# Inductor-based_non-neighbor_balancing_ar.net
KiCad netlist of a schematic drawn in EAGLE
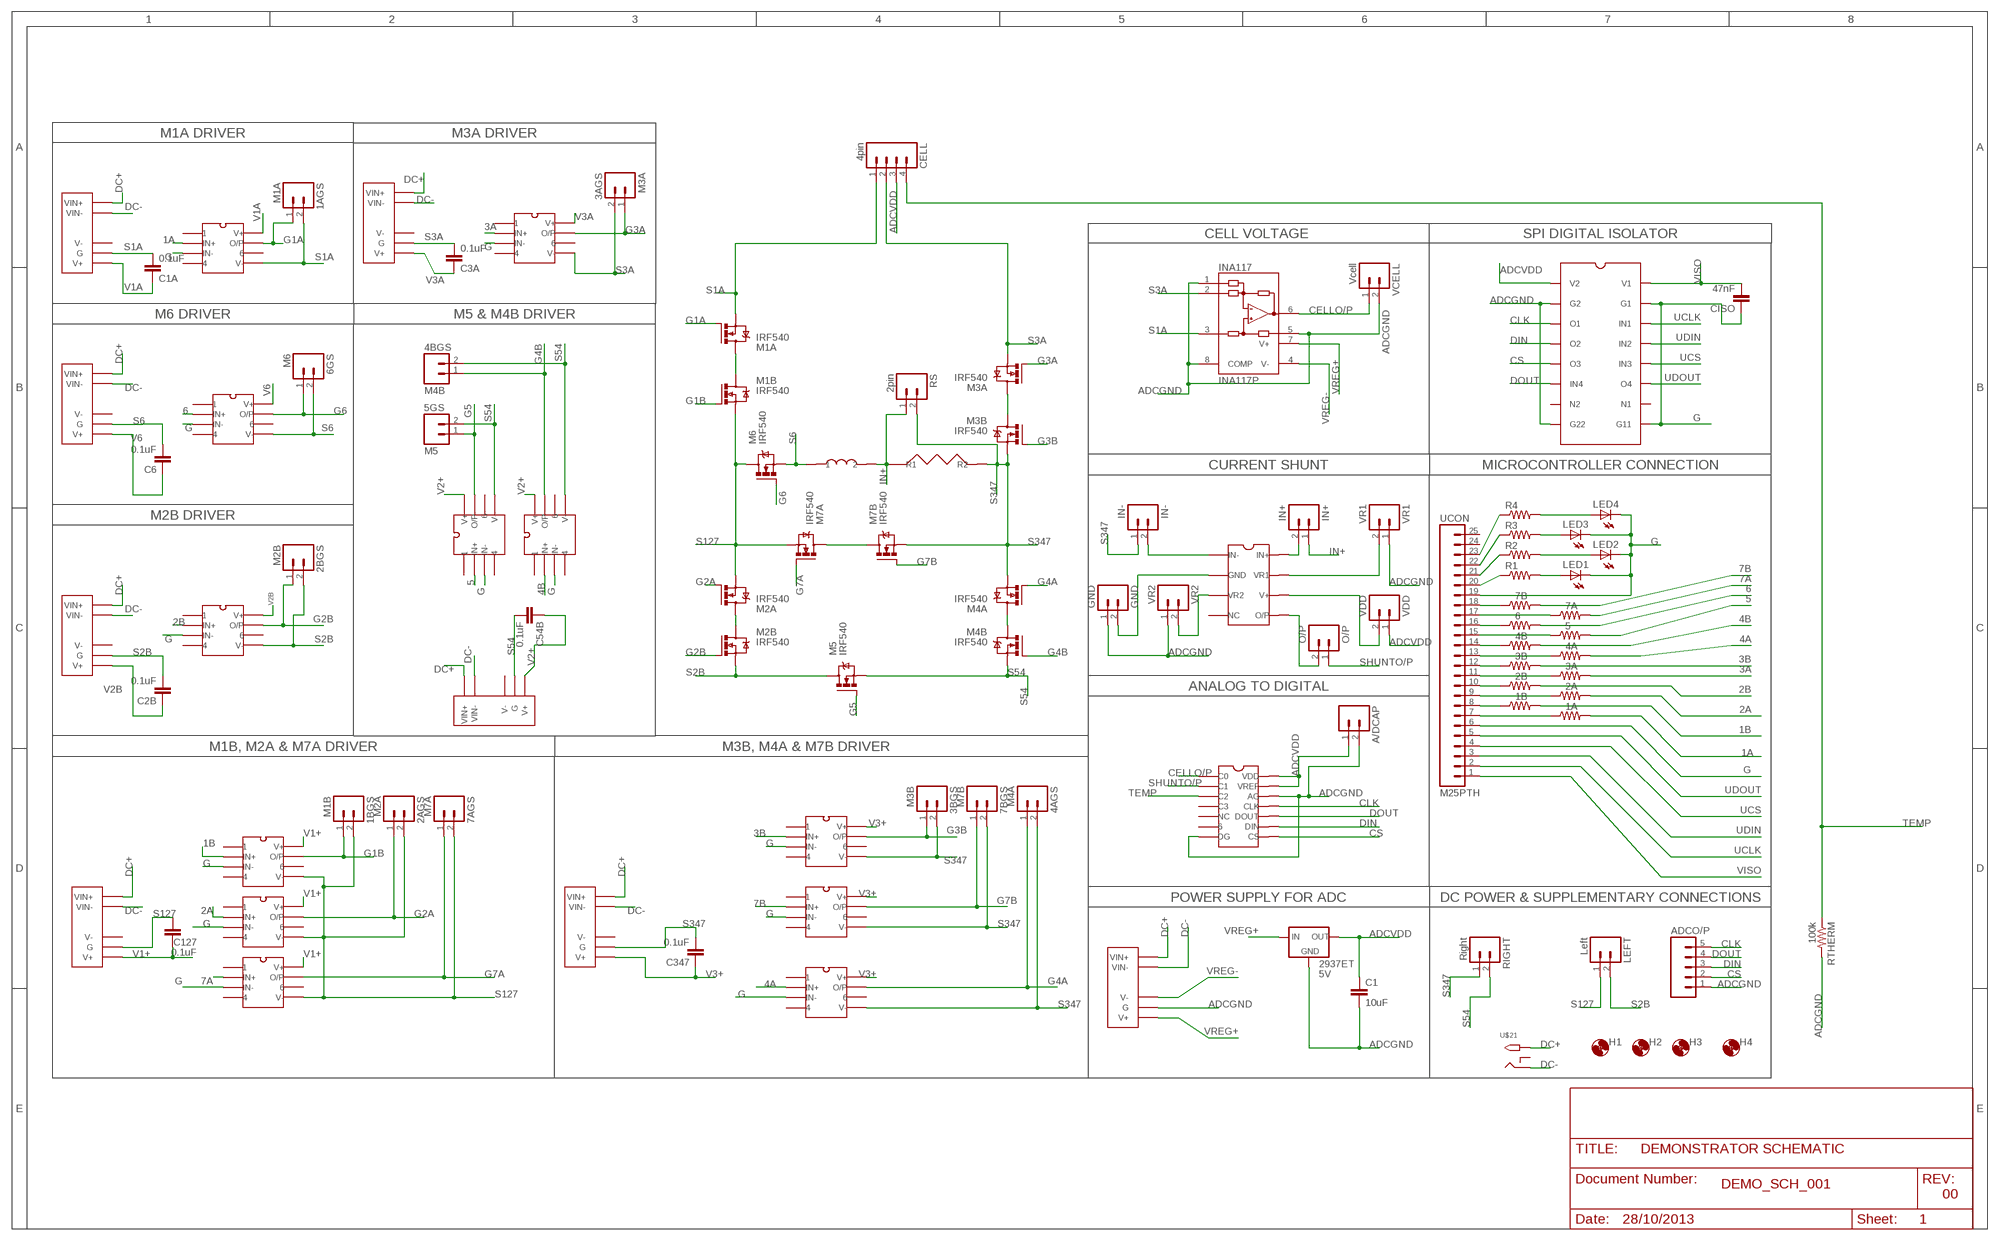
[diagram p0: schematic, sheet 1]

(export (version "E")
  (design (tool "Eeschema 10.0.6"))
  (components
    (comp (ref "1A")
      (value "220")
      (footprint "eagle-import:AXIAL-0.5")
      (libsource (lib "eagle-import") (part "RESISTORPTH-1/2W"))
    )
    (comp (ref "1AGS")
      (value "M1A")
      (footprint "eagle-import:1X02")
      (libsource (lib "eagle-import") (part "M02PTH"))
    )
    (comp (ref "1B")
      (value "220")
      (footprint "eagle-import:AXIAL-0.5")
      (libsource (lib "eagle-import") (part "RESISTORPTH-1/2W"))
    )
    (comp (ref "1BGS")
      (value "M1B")
      (footprint "eagle-import:1X02")
      (libsource (lib "eagle-import") (part "M02PTH"))
    )
    (comp (ref "2A")
      (value "220")
      (footprint "eagle-import:AXIAL-0.5")
      (libsource (lib "eagle-import") (part "RESISTORPTH-1/2W"))
    )
    (comp (ref "2AGS")
      (value "M2A")
      (footprint "eagle-import:1X02")
      (libsource (lib "eagle-import") (part "M02PTH"))
    )
    (comp (ref "2B")
      (value "220")
      (footprint "eagle-import:AXIAL-0.5")
      (libsource (lib "eagle-import") (part "RESISTORPTH-1/2W"))
    )
    (comp (ref "2BGS")
      (value "M2B")
      (footprint "eagle-import:1X02")
      (libsource (lib "eagle-import") (part "M02PTH"))
    )
    (comp (ref "3A")
      (value "220")
      (footprint "eagle-import:AXIAL-0.5")
      (libsource (lib "eagle-import") (part "RESISTORPTH-1/2W"))
    )
    (comp (ref "3AGS")
      (value "M3A")
      (footprint "eagle-import:1X02")
      (libsource (lib "eagle-import") (part "M02PTH"))
    )
    (comp (ref "3B")
      (value "220")
      (footprint "eagle-import:AXIAL-0.5")
      (libsource (lib "eagle-import") (part "RESISTORPTH-1/2W"))
    )
    (comp (ref "3BGS")
      (value "M3B")
      (footprint "eagle-import:1X02")
      (libsource (lib "eagle-import") (part "M02PTH"))
    )
    (comp (ref "4A")
      (value "220")
      (footprint "eagle-import:AXIAL-0.5")
      (libsource (lib "eagle-import") (part "RESISTORPTH-1/2W"))
    )
    (comp (ref "4AGS")
      (value "M4A")
      (footprint "eagle-import:1X02")
      (libsource (lib "eagle-import") (part "M02PTH"))
    )
    (comp (ref "4B")
      (value "220")
      (footprint "eagle-import:AXIAL-0.5")
      (libsource (lib "eagle-import") (part "RESISTORPTH-1/2W"))
    )
    (comp (ref "4BGS")
      (value "M4B")
      (footprint "eagle-import:1X02")
      (libsource (lib "eagle-import") (part "M02PTH"))
    )
    (comp (ref "5")
      (value "220")
      (footprint "eagle-import:AXIAL-0.5")
      (libsource (lib "eagle-import") (part "RESISTORPTH-1/2W"))
    )
    (comp (ref "5GS")
      (value "M5")
      (footprint "eagle-import:1X02")
      (libsource (lib "eagle-import") (part "M02PTH"))
    )
    (comp (ref "6")
      (value "220")
      (footprint "eagle-import:AXIAL-0.5")
      (libsource (lib "eagle-import") (part "RESISTORPTH-1/2W"))
    )
    (comp (ref "6GS")
      (value "M6")
      (footprint "eagle-import:1X02")
      (libsource (lib "eagle-import") (part "M02PTH"))
    )
    (comp (ref "7A")
      (value "220")
      (footprint "eagle-import:AXIAL-0.5")
      (libsource (lib "eagle-import") (part "RESISTORPTH-1/2W"))
    )
    (comp (ref "7AGS")
      (value "M7A")
      (footprint "eagle-import:1X02")
      (libsource (lib "eagle-import") (part "M02PTH"))
    )
    (comp (ref "7B")
      (value "220")
      (footprint "eagle-import:AXIAL-0.5")
      (libsource (lib "eagle-import") (part "RESISTORPTH-1/2W"))
    )
    (comp (ref "7BGS")
      (value "M7B")
      (footprint "eagle-import:1X02")
      (libsource (lib "eagle-import") (part "M02PTH"))
    )
    (comp (ref "2937ET")
      (value "5V")
      (footprint "eagle-import:78XXS")
      (libsource (lib "eagle-import") (part "78XXS"))
    )
    (comp (ref "A/DCAP")
      (value "M02PTH")
      (footprint "eagle-import:1X02")
      (libsource (lib "eagle-import") (part "M02PTH"))
    )
    (comp (ref "AD8210")
      (value "CSM")
      (footprint "eagle-import:CSM")
      (libsource (lib "eagle-import") (part "CSM"))
    )
    (comp (ref "ADC")
      (value "ADC")
      (footprint "eagle-import:DIL14")
      (libsource (lib "eagle-import") (part "ADC"))
    )
    (comp (ref "ADCO/P")
      (value "M05PTH")
      (footprint "eagle-import:1X05")
      (libsource (lib "eagle-import") (part "M05PTH"))
    )
    (comp (ref "C1")
      (value "10uF")
      (footprint "eagle-import:CAP-PTH-5MM")
      (libsource (lib "eagle-import") (part "CAPPTH1"))
    )
    (comp (ref "C1A")
      (value "0.1uF")
      (footprint "eagle-import:CAP-PTH-5MM")
      (libsource (lib "eagle-import") (part "SparkFun-Passives_CAPPTH1"))
    )
    (comp (ref "C2B")
      (value "0.1uF")
      (footprint "eagle-import:CAP-PTH-5MM")
      (libsource (lib "eagle-import") (part "SparkFun-Passives_CAPPTH1"))
    )
    (comp (ref "C3A")
      (value "0.1uF")
      (footprint "eagle-import:CAP-PTH-5MM")
      (libsource (lib "eagle-import") (part "SparkFun-Passives_CAPPTH1"))
    )
    (comp (ref "C6")
      (value "0.1uF")
      (footprint "eagle-import:CAP-PTH-5MM")
      (libsource (lib "eagle-import") (part "SparkFun-Passives_CAPPTH1"))
    )
    (comp (ref "C54B")
      (value "0.1uF")
      (footprint "eagle-import:CAP-PTH-5MM")
      (libsource (lib "eagle-import") (part "SparkFun-Passives_CAPPTH1"))
    )
    (comp (ref "C127")
      (value "0.1uF")
      (footprint "eagle-import:CAP-PTH-5MM")
      (libsource (lib "eagle-import") (part "SparkFun-Passives_CAPPTH1"))
    )
    (comp (ref "C347")
      (value "0.1uF")
      (footprint "eagle-import:CAP-PTH-5MM")
      (libsource (lib "eagle-import") (part "SparkFun-Passives_CAPPTH1"))
    )
    (comp (ref "CELL")
      (value "4pin")
      (footprint "eagle-import:1X04")
      (libsource (lib "eagle-import") (part "M04PTH"))
    )
    (comp (ref "CISO")
      (value "47nF")
      (footprint "eagle-import:CAP-PTH-5MM")
      (libsource (lib "eagle-import") (part "SparkFun-Passives_CAPPTH1"))
    )
    (comp (ref "DC/DC-ADC")
      (value "ADC")
      (footprint "eagle-import:DC-DC")
      (libsource (lib "eagle-import") (part "DC-DC"))
    )
    (comp (ref "DC/DC1A")
      (value "1A")
      (footprint "eagle-import:DC-DC")
      (libsource (lib "eagle-import") (part "DC-DC"))
    )
    (comp (ref "DC/DC2B")
      (value "2B")
      (footprint "eagle-import:DC-DC")
      (libsource (lib "eagle-import") (part "DC-DC"))
    )
    (comp (ref "DC/DC3A")
      (value "3A")
      (footprint "eagle-import:DC-DC")
      (libsource (lib "eagle-import") (part "DC-DC"))
    )
    (comp (ref "DC/DC6")
      (value "6")
      (footprint "eagle-import:DC-DC")
      (libsource (lib "eagle-import") (part "DC-DC"))
    )
    (comp (ref "DC/DC45")
      (value "4B5")
      (footprint "eagle-import:DC-DC")
      (libsource (lib "eagle-import") (part "DC-DC"))
    )
    (comp (ref "DC/DC127")
      (value "1B2A7A")
      (footprint "eagle-import:DC-DC")
      (libsource (lib "eagle-import") (part "DC-DC"))
    )
    (comp (ref "DC/DC347")
      (value "3B4A7B")
      (footprint "eagle-import:DC-DC")
      (libsource (lib "eagle-import") (part "DC-DC"))
    )
    (comp (ref "GND")
      (value "GND")
      (footprint "eagle-import:1X02")
      (libsource (lib "eagle-import") (part "M02PTH"))
    )
    (comp (ref "H1")
      (value "MOUNT-HOLE3.0")
      (footprint "eagle-import:3,0")
      (libsource (lib "eagle-import") (part "MOUNT-HOLE3.0"))
    )
    (comp (ref "H2")
      (value "MOUNT-HOLE3.0")
      (footprint "eagle-import:3,0")
      (libsource (lib "eagle-import") (part "MOUNT-HOLE3.0"))
    )
    (comp (ref "H3")
      (value "MOUNT-HOLE3.0")
      (footprint "eagle-import:3,0")
      (libsource (lib "eagle-import") (part "MOUNT-HOLE3.0"))
    )
    (comp (ref "H4")
      (value "MOUNT-HOLE3.0")
      (footprint "eagle-import:3,0")
      (libsource (lib "eagle-import") (part "MOUNT-HOLE3.0"))
    )
    (comp (ref "HCPL902J")
      (value "HCPL902")
      (footprint "eagle-import:HCPL902")
      (libsource (lib "eagle-import") (part "HCPL902"))
    )
    (comp (ref "IN+")
      (value "IN+")
      (footprint "eagle-import:1X02")
      (libsource (lib "eagle-import") (part "M02PTH"))
    )
    (comp (ref "IN-")
      (value "IN-")
      (footprint "eagle-import:1X02")
      (libsource (lib "eagle-import") (part "M02PTH"))
    )
    (comp (ref "INA117")
      (value "INA117P")
      (footprint "eagle-import:DIL08")
      (fields (field (name "MF") "TEXAS INSTRUMENTS"))
      (libsource (lib "eagle-import") (part "INA117P"))
    )
    (comp (ref "LED1")
      (value "LEDCHIPLED_0805")
      (footprint "eagle-import:CHIPLED_0805")
      (libsource (lib "eagle-import") (part "LEDCHIPLED_0805"))
    )
    (comp (ref "LED2")
      (value "LEDCHIPLED_0805")
      (footprint "eagle-import:CHIPLED_0805")
      (libsource (lib "eagle-import") (part "LEDCHIPLED_0805"))
    )
    (comp (ref "LED3")
      (value "LEDCHIPLED_0805")
      (footprint "eagle-import:CHIPLED_0805")
      (libsource (lib "eagle-import") (part "LEDCHIPLED_0805"))
    )
    (comp (ref "LED4")
      (value "LEDCHIPLED_0805")
      (footprint "eagle-import:CHIPLED_0805")
      (libsource (lib "eagle-import") (part "LEDCHIPLED_0805"))
    )
    (comp (ref "LEFT")
      (value "Left")
      (footprint "eagle-import:1X02")
      (libsource (lib "eagle-import") (part "M02PTH"))
    )
    (comp (ref "M1A")
      (value "IRF540")
      (footprint "eagle-import:TO220BV")
      (libsource (lib "eagle-import") (part "IRF540"))
    )
    (comp (ref "M1AD")
      (value "M1A")
      (footprint "eagle-import:OPTO3180")
      (libsource (lib "eagle-import") (part "OPTO3180"))
    )
    (comp (ref "M1B")
      (value "IRF540")
      (footprint "eagle-import:TO220BV")
      (libsource (lib "eagle-import") (part "IRF540"))
    )
    (comp (ref "M1BD")
      (value "M1B")
      (footprint "eagle-import:OPTO3180")
      (libsource (lib "eagle-import") (part "OPTO3180"))
    )
    (comp (ref "M2A")
      (value "IRF540")
      (footprint "eagle-import:TO220BV")
      (libsource (lib "eagle-import") (part "IRF540"))
    )
    (comp (ref "M2AD")
      (value "M2A")
      (footprint "eagle-import:OPTO3180")
      (libsource (lib "eagle-import") (part "OPTO3180"))
    )
    (comp (ref "M2B")
      (value "IRF540")
      (footprint "eagle-import:TO220BV")
      (libsource (lib "eagle-import") (part "IRF540"))
    )
    (comp (ref "M2BD")
      (value "M2B")
      (footprint "eagle-import:OPTO3180")
      (libsource (lib "eagle-import") (part "OPTO3180"))
    )
    (comp (ref "M3A")
      (value "IRF540")
      (footprint "eagle-import:TO220BV")
      (libsource (lib "eagle-import") (part "IRF540"))
    )
    (comp (ref "M3AD")
      (value "M3A")
      (footprint "eagle-import:OPTO3180")
      (libsource (lib "eagle-import") (part "OPTO3180"))
    )
    (comp (ref "M3B")
      (value "IRF540")
      (footprint "eagle-import:TO220BV")
      (libsource (lib "eagle-import") (part "IRF540"))
    )
    (comp (ref "M3BD")
      (value "M3B")
      (footprint "eagle-import:OPTO3180")
      (libsource (lib "eagle-import") (part "OPTO3180"))
    )
    (comp (ref "M4A")
      (value "IRF540")
      (footprint "eagle-import:TO220BV")
      (libsource (lib "eagle-import") (part "IRF540"))
    )
    (comp (ref "M4AD")
      (value "M4A")
      (footprint "eagle-import:OPTO3180")
      (libsource (lib "eagle-import") (part "OPTO3180"))
    )
    (comp (ref "M4B")
      (value "IRF540")
      (footprint "eagle-import:TO220BV")
      (libsource (lib "eagle-import") (part "IRF540"))
    )
    (comp (ref "M4BD")
      (value "M4B")
      (footprint "eagle-import:OPTO3180")
      (libsource (lib "eagle-import") (part "OPTO3180"))
    )
    (comp (ref "M5")
      (value "IRF540")
      (footprint "eagle-import:TO220BV")
      (libsource (lib "eagle-import") (part "IRF540"))
    )
    (comp (ref "M5D")
      (value "M5")
      (footprint "eagle-import:OPTO3180")
      (libsource (lib "eagle-import") (part "OPTO3180"))
    )
    (comp (ref "M6")
      (value "IRF540")
      (footprint "eagle-import:TO220BV")
      (libsource (lib "eagle-import") (part "IRF540"))
    )
    (comp (ref "M6D")
      (value "M6")
      (footprint "eagle-import:OPTO3180")
      (libsource (lib "eagle-import") (part "OPTO3180"))
    )
    (comp (ref "M7A")
      (value "IRF540")
      (footprint "eagle-import:TO220BV")
      (libsource (lib "eagle-import") (part "IRF540"))
    )
    (comp (ref "M7AD")
      (value "M7A")
      (footprint "eagle-import:OPTO3180")
      (libsource (lib "eagle-import") (part "OPTO3180"))
    )
    (comp (ref "M7B")
      (value "IRF540")
      (footprint "eagle-import:TO220BV")
      (libsource (lib "eagle-import") (part "IRF540"))
    )
    (comp (ref "M7BD")
      (value "M7B")
      (footprint "eagle-import:OPTO3180")
      (libsource (lib "eagle-import") (part "OPTO3180"))
    )
    (comp (ref "O/P")
      (value "O/P")
      (footprint "eagle-import:1X02")
      (libsource (lib "eagle-import") (part "M02PTH"))
    )
    (comp (ref "R1")
      (value "R-US_R0805")
      (footprint "eagle-import:R0805")
      (libsource (lib "eagle-import") (part "R-US_R0805"))
    )
    (comp (ref "R2")
      (value "R-US_R0805")
      (footprint "eagle-import:R0805")
      (libsource (lib "eagle-import") (part "R-US_R0805"))
    )
    (comp (ref "R3")
      (value "R-US_R0805")
      (footprint "eagle-import:R0805")
      (libsource (lib "eagle-import") (part "R-US_R0805"))
    )
    (comp (ref "R4")
      (value "R-US_R0805")
      (footprint "eagle-import:R0805")
      (libsource (lib "eagle-import") (part "R-US_R0805"))
    )
    (comp (ref "RIGHT")
      (value "Right")
      (footprint "eagle-import:1X02")
      (libsource (lib "eagle-import") (part "M02PTH"))
    )
    (comp (ref "RS")
      (value "2pin")
      (footprint "eagle-import:1X02")
      (libsource (lib "eagle-import") (part "M02PTH"))
    )
    (comp (ref "RTHERM")
      (value "100k")
      (footprint "eagle-import:AXIAL-0.5")
      (libsource (lib "eagle-import") (part "RESISTORPTH-1/2W"))
    )
    (comp (ref "U$1")
      (value "INDFINAL")
      (footprint "eagle-import:IND1MHFINAL")
      (libsource (lib "eagle-import") (part "INDFINAL"))
    )
    (comp (ref "U$3")
      (value "RSHUNT")
      (footprint "eagle-import:RSHUNT")
      (libsource (lib "eagle-import") (part "RSHUNT"))
    )
    (comp (ref "U$21")
      (value "2.1MMJACKTHM")
      (footprint "eagle-import:PJ-102A")
      (libsource (lib "eagle-import") (part "2.1MMJACKTHM"))
    )
    (comp (ref "UCON")
      (value "M25PTH")
      (footprint "eagle-import:1X25")
      (libsource (lib "eagle-import") (part "M25PTH"))
    )
    (comp (ref "VCELL")
      (value "Vcell")
      (footprint "eagle-import:1X02")
      (libsource (lib "eagle-import") (part "M02PTH"))
    )
    (comp (ref "VDD")
      (value "VDD")
      (footprint "eagle-import:1X02")
      (libsource (lib "eagle-import") (part "M02PTH"))
    )
    (comp (ref "VR1")
      (value "VR1")
      (footprint "eagle-import:1X02")
      (libsource (lib "eagle-import") (part "M02PTH"))
    )
    (comp (ref "VR2")
      (value "VR2")
      (footprint "eagle-import:1X02")
      (libsource (lib "eagle-import") (part "M02PTH"))
    )
  )
  (nets
    (net (code "1") (name "/1A") (class "Default")
      (node (ref "1A") (pin "P$2") (pinfunction "2_P$2") (pintype "passive"))
      (node (ref "M1AD") (pin "IN+") (pinfunction "IN+_IN+") (pintype "bidirectional"))
    )
    (net (code "2") (name "/1B") (class "Default")
      (node (ref "1B") (pin "P$2") (pinfunction "2_P$2") (pintype "passive"))
      (node (ref "M1BD") (pin "IN+") (pinfunction "IN+_IN+") (pintype "bidirectional"))
    )
    (net (code "3") (name "/2A") (class "Default")
      (node (ref "2A") (pin "P$2") (pinfunction "2_P$2") (pintype "passive"))
      (node (ref "M2AD") (pin "IN+") (pinfunction "IN+_IN+") (pintype "bidirectional"))
    )
    (net (code "4") (name "/2B") (class "Default")
      (node (ref "2B") (pin "P$2") (pinfunction "2_P$2") (pintype "passive"))
      (node (ref "M2BD") (pin "IN+") (pinfunction "IN+_IN+") (pintype "bidirectional"))
    )
    (net (code "5") (name "/3A") (class "Default")
      (node (ref "3A") (pin "P$2") (pinfunction "2_P$2") (pintype "passive"))
      (node (ref "M3AD") (pin "IN+") (pinfunction "IN+_IN+") (pintype "bidirectional"))
    )
    (net (code "6") (name "/3B") (class "Default")
      (node (ref "3B") (pin "P$2") (pinfunction "2_P$2") (pintype "passive"))
      (node (ref "M3BD") (pin "IN+") (pinfunction "IN+_IN+") (pintype "bidirectional"))
    )
    (net (code "7") (name "/4A") (class "Default")
      (node (ref "4A") (pin "P$2") (pinfunction "2_P$2") (pintype "passive"))
      (node (ref "M4AD") (pin "IN+") (pinfunction "IN+_IN+") (pintype "bidirectional"))
    )
    (net (code "8") (name "/4B") (class "Default")
      (node (ref "4B") (pin "P$2") (pinfunction "2_P$2") (pintype "passive"))
      (node (ref "M4BD") (pin "IN+") (pinfunction "IN+_IN+") (pintype "bidirectional"))
    )
    (net (code "9") (name "/5") (class "Default")
      (node (ref "5") (pin "P$2") (pinfunction "2_P$2") (pintype "passive"))
      (node (ref "M5D") (pin "IN+") (pinfunction "IN+_IN+") (pintype "bidirectional"))
    )
    (net (code "10") (name "/6") (class "Default")
      (node (ref "6") (pin "P$2") (pinfunction "2_P$2") (pintype "passive"))
      (node (ref "M6D") (pin "IN+") (pinfunction "IN+_IN+") (pintype "bidirectional"))
    )
    (net (code "11") (name "/7A") (class "Default")
      (node (ref "7A") (pin "P$2") (pinfunction "2_P$2") (pintype "passive"))
      (node (ref "M7AD") (pin "IN+") (pinfunction "IN+_IN+") (pintype "bidirectional"))
    )
    (net (code "12") (name "/7B") (class "Default")
      (node (ref "7B") (pin "P$2") (pinfunction "2_P$2") (pintype "passive"))
      (node (ref "M7BD") (pin "IN+") (pinfunction "IN+_IN+") (pintype "bidirectional"))
    )
    (net (code "13") (name "/ADCGND") (class "Default")
      (node (ref "2937ET") (pin "GND") (pinfunction "GND_GND") (pintype "input"))
      (node (ref "A/DCAP") (pin "2") (pinfunction "2_2") (pintype "passive"))
      (node (ref "ADC") (pin "AGND") (pinfunction "AG_AGND") (pintype "bidirectional"))
      (node (ref "ADC") (pin "DGND") (pinfunction "DG_DGND") (pintype "bidirectional"))
      (node (ref "ADCO/P") (pin "1") (pinfunction "1_1") (pintype "passive"))
      (node (ref "C1") (pin "2") (pinfunction "2_2") (pintype "passive"))
      (node (ref "DC/DC-ADC") (pin "G") (pinfunction "G_G") (pintype "bidirectional"))
      (node (ref "GND") (pin "1") (pinfunction "1_1") (pintype "passive"))
      (node (ref "HCPL902J") (pin "G2") (pinfunction "G2_G2") (pintype "bidirectional"))
      (node (ref "HCPL902J") (pin "G22") (pinfunction "G22_G22") (pintype "bidirectional"))
      (node (ref "INA117") (pin "1") (pinfunction "REFB_1") (pintype "input"))
      (node (ref "INA117") (pin "5") (pinfunction "REFA_5") (pintype "input"))
      (node (ref "INA117") (pin "8") (pinfunction "COMP_8") (pintype "passive"))
      (node (ref "RTHERM") (pin "P$2") (pinfunction "2_P$2") (pintype "passive"))
      (node (ref "VCELL") (pin "2") (pinfunction "2_2") (pintype "passive"))
      (node (ref "VR1") (pin "1") (pinfunction "1_1") (pintype "passive"))
      (node (ref "VR2") (pin "1") (pinfunction "1_1") (pintype "passive"))
    )
    (net (code "14") (name "/ADCVDD") (class "Default")
      (node (ref "2937ET") (pin "OUT") (pinfunction "OUT_OUT") (pintype "passive"))
      (node (ref "A/DCAP") (pin "1") (pinfunction "1_1") (pintype "passive"))
      (node (ref "ADC") (pin "VDD") (pinfunction "VDD_VDD") (pintype "bidirectional"))
      (node (ref "ADC") (pin "VREF") (pinfunction "VREF_VREF") (pintype "bidirectional"))
      (node (ref "C1") (pin "1") (pinfunction "1_1") (pintype "passive"))
      (node (ref "CELL") (pin "3") (pinfunction "3_3") (pintype "passive"))
      (node (ref "HCPL902J") (pin "V2") (pinfunction "V2_V2") (pintype "bidirectional"))
      (node (ref "VDD") (pin "1") (pinfunction "1_1") (pintype "passive"))
    )
    (net (code "15") (name "/CELLO{slash}P") (class "Default")
      (node (ref "ADC") (pin "CH0") (pinfunction "C0_CH0") (pintype "bidirectional"))
      (node (ref "INA117") (pin "6") (pinfunction "OUT_6") (pintype "output"))
      (node (ref "VCELL") (pin "1") (pinfunction "1_1") (pintype "passive"))
    )
    (net (code "16") (name "/CLK") (class "Default")
      (node (ref "ADC") (pin "CLK") (pinfunction "CLK_CLK") (pintype "bidirectional"))
      (node (ref "ADCO/P") (pin "5") (pinfunction "5_5") (pintype "passive"))
      (node (ref "HCPL902J") (pin "OUT1") (pinfunction "O1_OUT1") (pintype "bidirectional"))
    )
    (net (code "17") (name "/CS") (class "Default")
      (node (ref "ADC") (pin "CS") (pinfunction "CS_CS") (pintype "bidirectional"))
      (node (ref "ADCO/P") (pin "2") (pinfunction "2_2") (pintype "passive"))
      (node (ref "HCPL902J") (pin "OUT3") (pinfunction "O3_OUT3") (pintype "bidirectional"))
    )
    (net (code "18") (name "/DC+") (class "Default")
      (node (ref "DC/DC-ADC") (pin "VIN+") (pinfunction "VIN+_VIN+") (pintype "bidirectional"))
      (node (ref "DC/DC127") (pin "VIN+") (pinfunction "VIN+_VIN+") (pintype "bidirectional"))
      (node (ref "DC/DC1A") (pin "VIN+") (pinfunction "VIN+_VIN+") (pintype "bidirectional"))
      (node (ref "DC/DC2B") (pin "VIN+") (pinfunction "VIN+_VIN+") (pintype "bidirectional"))
      (node (ref "DC/DC347") (pin "VIN+") (pinfunction "VIN+_VIN+") (pintype "bidirectional"))
      (node (ref "DC/DC3A") (pin "VIN+") (pinfunction "VIN+_VIN+") (pintype "bidirectional"))
      (node (ref "DC/DC45") (pin "VIN+") (pinfunction "VIN+_VIN+") (pintype "bidirectional"))
      (node (ref "DC/DC6") (pin "VIN+") (pinfunction "VIN+_VIN+") (pintype "bidirectional"))
      (node (ref "U$21") (pin "TIP") (pinfunction "TIP_TIP") (pintype "bidirectional"))
    )
    (net (code "19") (name "/DC-") (class "Default")
      (node (ref "DC/DC-ADC") (pin "VIN-") (pinfunction "VIN-_VIN-") (pintype "bidirectional"))
      (node (ref "DC/DC127") (pin "VIN-") (pinfunction "VIN-_VIN-") (pintype "bidirectional"))
      (node (ref "DC/DC1A") (pin "VIN-") (pinfunction "VIN-_VIN-") (pintype "bidirectional"))
      (node (ref "DC/DC2B") (pin "VIN-") (pinfunction "VIN-_VIN-") (pintype "bidirectional"))
      (node (ref "DC/DC347") (pin "VIN-") (pinfunction "VIN-_VIN-") (pintype "bidirectional"))
      (node (ref "DC/DC3A") (pin "VIN-") (pinfunction "VIN-_VIN-") (pintype "bidirectional"))
      (node (ref "DC/DC45") (pin "VIN-") (pinfunction "VIN-_VIN-") (pintype "bidirectional"))
      (node (ref "DC/DC6") (pin "VIN-") (pinfunction "VIN-_VIN-") (pintype "bidirectional"))
      (node (ref "U$21") (pin "RING") (pinfunction "RING_RING") (pintype "bidirectional"))
    )
    (net (code "20") (name "/DIN") (class "Default")
      (node (ref "ADC") (pin "DIN") (pinfunction "DIN_DIN") (pintype "bidirectional"))
      (node (ref "ADCO/P") (pin "3") (pinfunction "3_3") (pintype "passive"))
      (node (ref "HCPL902J") (pin "OUT2") (pinfunction "O2_OUT2") (pintype "bidirectional"))
    )
    (net (code "21") (name "/DOUT") (class "Default")
      (node (ref "ADC") (pin "DOUT") (pinfunction "DOUT_DOUT") (pintype "bidirectional"))
      (node (ref "ADCO/P") (pin "4") (pinfunction "4_4") (pintype "passive"))
      (node (ref "HCPL902J") (pin "IN4") (pinfunction "IN4_IN4") (pintype "bidirectional"))
    )
    (net (code "22") (name "/G") (class "Default")
      (node (ref "CISO") (pin "1") (pinfunction "1_1") (pintype "passive"))
      (node (ref "HCPL902J") (pin "G1") (pinfunction "G1_G1") (pintype "bidirectional"))
      (node (ref "HCPL902J") (pin "G11") (pinfunction "G11_G11") (pintype "bidirectional"))
      (node (ref "LED1") (pin "C") (pinfunction "C_C") (pintype "passive"))
      (node (ref "LED2") (pin "C") (pinfunction "C_C") (pintype "passive"))
      (node (ref "LED3") (pin "C") (pinfunction "C_C") (pintype "passive"))
      (node (ref "LED4") (pin "C") (pinfunction "C_C") (pintype "passive"))
      (node (ref "M1AD") (pin "IN-") (pinfunction "IN-_IN-") (pintype "bidirectional"))
      (node (ref "M1BD") (pin "IN-") (pinfunction "IN-_IN-") (pintype "bidirectional"))
      (node (ref "M2AD") (pin "IN-") (pinfunction "IN-_IN-") (pintype "bidirectional"))
      (node (ref "M2BD") (pin "IN-") (pinfunction "IN-_IN-") (pintype "bidirectional"))
      (node (ref "M3AD") (pin "IN-") (pinfunction "IN-_IN-") (pintype "bidirectional"))
      (node (ref "M3BD") (pin "IN-") (pinfunction "IN-_IN-") (pintype "bidirectional"))
      (node (ref "M4AD") (pin "IN-") (pinfunction "IN-_IN-") (pintype "bidirectional"))
      (node (ref "M4BD") (pin "IN-") (pinfunction "IN-_IN-") (pintype "bidirectional"))
      (node (ref "M5D") (pin "IN-") (pinfunction "IN-_IN-") (pintype "bidirectional"))
      (node (ref "M6D") (pin "IN-") (pinfunction "IN-_IN-") (pintype "bidirectional"))
      (node (ref "M7AD") (pin "IN-") (pinfunction "IN-_IN-") (pintype "bidirectional"))
      (node (ref "M7BD") (pin "IN-") (pinfunction "IN-_IN-") (pintype "bidirectional"))
      (node (ref "UCON") (pin "19") (pinfunction "19_19") (pintype "passive"))
      (node (ref "UCON") (pin "6") (pinfunction "6_6") (pintype "passive"))
    )
    (net (code "23") (name "/G1A") (class "Default")
      (node (ref "1AGS") (pin "1") (pinfunction "1_1") (pintype "passive"))
      (node (ref "M1A") (pin "G") (pinfunction "G_G") (pintype "passive"))
      (node (ref "M1AD") (pin "O/P") (pinfunction "O/P_O/P") (pintype "bidirectional"))
    )
    (net (code "24") (name "/G1B") (class "Default")
      (node (ref "1BGS") (pin "1") (pinfunction "1_1") (pintype "passive"))
      (node (ref "M1B") (pin "G") (pinfunction "G_G") (pintype "passive"))
      (node (ref "M1BD") (pin "O/P") (pinfunction "O/P_O/P") (pintype "bidirectional"))
    )
    (net (code "25") (name "/G2A") (class "Default")
      (node (ref "2AGS") (pin "1") (pinfunction "1_1") (pintype "passive"))
      (node (ref "M2A") (pin "G") (pinfunction "G_G") (pintype "passive"))
      (node (ref "M2AD") (pin "O/P") (pinfunction "O/P_O/P") (pintype "bidirectional"))
    )
    (net (code "26") (name "/G2B") (class "Default")
      (node (ref "2BGS") (pin "1") (pinfunction "1_1") (pintype "passive"))
      (node (ref "M2B") (pin "G") (pinfunction "G_G") (pintype "passive"))
      (node (ref "M2BD") (pin "O/P") (pinfunction "O/P_O/P") (pintype "bidirectional"))
    )
    (net (code "27") (name "/G3A") (class "Default")
      (node (ref "3AGS") (pin "1") (pinfunction "1_1") (pintype "passive"))
      (node (ref "M3A") (pin "G") (pinfunction "G_G") (pintype "passive"))
      (node (ref "M3AD") (pin "O/P") (pinfunction "O/P_O/P") (pintype "bidirectional"))
    )
    (net (code "28") (name "/G3B") (class "Default")
      (node (ref "3BGS") (pin "1") (pinfunction "1_1") (pintype "passive"))
      (node (ref "M3B") (pin "G") (pinfunction "G_G") (pintype "passive"))
      (node (ref "M3BD") (pin "O/P") (pinfunction "O/P_O/P") (pintype "bidirectional"))
    )
    (net (code "29") (name "/G4A") (class "Default")
      (node (ref "4AGS") (pin "1") (pinfunction "1_1") (pintype "passive"))
      (node (ref "M4A") (pin "G") (pinfunction "G_G") (pintype "passive"))
      (node (ref "M4AD") (pin "O/P") (pinfunction "O/P_O/P") (pintype "bidirectional"))
    )
    (net (code "30") (name "/G4B") (class "Default")
      (node (ref "4BGS") (pin "1") (pinfunction "1_1") (pintype "passive"))
      (node (ref "M4B") (pin "G") (pinfunction "G_G") (pintype "passive"))
      (node (ref "M4BD") (pin "O/P") (pinfunction "O/P_O/P") (pintype "bidirectional"))
    )
    (net (code "31") (name "/G5") (class "Default")
      (node (ref "5GS") (pin "1") (pinfunction "1_1") (pintype "passive"))
      (node (ref "M5") (pin "G") (pinfunction "G_G") (pintype "passive"))
      (node (ref "M5D") (pin "O/P") (pinfunction "O/P_O/P") (pintype "bidirectional"))
    )
    (net (code "32") (name "/G6") (class "Default")
      (node (ref "6GS") (pin "1") (pinfunction "1_1") (pintype "passive"))
      (node (ref "M6") (pin "G") (pinfunction "G_G") (pintype "passive"))
      (node (ref "M6D") (pin "O/P") (pinfunction "O/P_O/P") (pintype "bidirectional"))
    )
    (net (code "33") (name "/G7A") (class "Default")
      (node (ref "7AGS") (pin "1") (pinfunction "1_1") (pintype "passive"))
      (node (ref "M7A") (pin "G") (pinfunction "G_G") (pintype "passive"))
      (node (ref "M7AD") (pin "O/P") (pinfunction "O/P_O/P") (pintype "bidirectional"))
    )
    (net (code "34") (name "/G7B") (class "Default")
      (node (ref "7BGS") (pin "1") (pinfunction "1_1") (pintype "passive"))
      (node (ref "M7B") (pin "G") (pinfunction "G_G") (pintype "passive"))
      (node (ref "M7BD") (pin "O/P") (pinfunction "O/P_O/P") (pintype "bidirectional"))
    )
    (net (code "35") (name "/IN+") (class "Default")
      (node (ref "IN+") (pin "1") (pinfunction "1_1") (pintype "passive"))
      (node (ref "RS") (pin "1") (pinfunction "1_1") (pintype "passive"))
      (node (ref "U$1") (pin "2") (pinfunction "2_2") (pintype "bidirectional"))
      (node (ref "U$3") (pin "R1") (pinfunction "R1_R1") (pintype "bidirectional"))
    )
    (net (code "36") (name "/S1A") (class "Default")
      (node (ref "1AGS") (pin "2") (pinfunction "2_2") (pintype "passive"))
      (node (ref "C1A") (pin "2") (pinfunction "2_2") (pintype "passive"))
      (node (ref "CELL") (pin "1") (pinfunction "1_1") (pintype "passive"))
      (node (ref "DC/DC1A") (pin "G") (pinfunction "G_G") (pintype "bidirectional"))
      (node (ref "INA117") (pin "3") (pinfunction "+IN_3") (pintype "input"))
      (node (ref "M1A") (pin "S") (pinfunction "S_S") (pintype "passive"))
      (node (ref "M1AD") (pin "V-") (pinfunction "V-_V-") (pintype "bidirectional"))
    )
    (net (code "37") (name "/S2B") (class "Default")
      (node (ref "2BGS") (pin "2") (pinfunction "2_2") (pintype "passive"))
      (node (ref "C2B") (pin "2") (pinfunction "2_2") (pintype "passive"))
      (node (ref "DC/DC2B") (pin "G") (pinfunction "G_G") (pintype "bidirectional"))
      (node (ref "LEFT") (pin "2") (pinfunction "2_2") (pintype "passive"))
      (node (ref "M2B") (pin "S") (pinfunction "S_S") (pintype "passive"))
      (node (ref "M2BD") (pin "V-") (pinfunction "V-_V-") (pintype "bidirectional"))
      (node (ref "M5") (pin "D") (pinfunction "D_D") (pintype "passive"))
    )
    (net (code "38") (name "/S3A") (class "Default")
      (node (ref "3AGS") (pin "2") (pinfunction "2_2") (pintype "passive"))
      (node (ref "C3A") (pin "2") (pinfunction "2_2") (pintype "passive"))
      (node (ref "CELL") (pin "2") (pinfunction "2_2") (pintype "passive"))
      (node (ref "DC/DC3A") (pin "G") (pinfunction "G_G") (pintype "bidirectional"))
      (node (ref "INA117") (pin "2") (pinfunction "-IN_2") (pintype "input"))
      (node (ref "M3A") (pin "S") (pinfunction "S_S") (pintype "passive"))
      (node (ref "M3AD") (pin "V-") (pinfunction "V-_V-") (pintype "bidirectional"))
    )
    (net (code "39") (name "/S6") (class "Default")
      (node (ref "6GS") (pin "2") (pinfunction "2_2") (pintype "passive"))
      (node (ref "C6") (pin "2") (pinfunction "2_2") (pintype "passive"))
      (node (ref "DC/DC6") (pin "G") (pinfunction "G_G") (pintype "bidirectional"))
      (node (ref "M6") (pin "S") (pinfunction "S_S") (pintype "passive"))
      (node (ref "M6D") (pin "V-") (pinfunction "V-_V-") (pintype "bidirectional"))
      (node (ref "U$1") (pin "1") (pinfunction "1_1") (pintype "bidirectional"))
    )
    (net (code "40") (name "/S54") (class "Default")
      (node (ref "4BGS") (pin "2") (pinfunction "2_2") (pintype "passive"))
      (node (ref "5GS") (pin "2") (pinfunction "2_2") (pintype "passive"))
      (node (ref "C54B") (pin "2") (pinfunction "2_2") (pintype "passive"))
      (node (ref "DC/DC45") (pin "G") (pinfunction "G_G") (pintype "bidirectional"))
      (node (ref "M4B") (pin "S") (pinfunction "S_S") (pintype "passive"))
      (node (ref "M4BD") (pin "V-") (pinfunction "V-_V-") (pintype "bidirectional"))
      (node (ref "M5") (pin "S") (pinfunction "S_S") (pintype "passive"))
      (node (ref "M5D") (pin "V-") (pinfunction "V-_V-") (pintype "bidirectional"))
      (node (ref "RIGHT") (pin "2") (pinfunction "2_2") (pintype "passive"))
    )
    (net (code "41") (name "/S127") (class "Default")
      (node (ref "1BGS") (pin "2") (pinfunction "2_2") (pintype "passive"))
      (node (ref "2AGS") (pin "2") (pinfunction "2_2") (pintype "passive"))
      (node (ref "7AGS") (pin "2") (pinfunction "2_2") (pintype "passive"))
      (node (ref "C127") (pin "2") (pinfunction "2_2") (pintype "passive"))
      (node (ref "DC/DC127") (pin "G") (pinfunction "G_G") (pintype "bidirectional"))
      (node (ref "LEFT") (pin "1") (pinfunction "1_1") (pintype "passive"))
      (node (ref "M1B") (pin "S") (pinfunction "S_S") (pintype "passive"))
      (node (ref "M1BD") (pin "V-") (pinfunction "V-_V-") (pintype "bidirectional"))
      (node (ref "M2A") (pin "S") (pinfunction "S_S") (pintype "passive"))
      (node (ref "M2AD") (pin "V-") (pinfunction "V-_V-") (pintype "bidirectional"))
      (node (ref "M6") (pin "D") (pinfunction "D_D") (pintype "passive"))
      (node (ref "M7A") (pin "S") (pinfunction "S_S") (pintype "passive"))
      (node (ref "M7AD") (pin "V-") (pinfunction "V-_V-") (pintype "bidirectional"))
    )
    (net (code "42") (name "/S347") (class "Default")
      (node (ref "3BGS") (pin "2") (pinfunction "2_2") (pintype "passive"))
      (node (ref "4AGS") (pin "2") (pinfunction "2_2") (pintype "passive"))
      (node (ref "7BGS") (pin "2") (pinfunction "2_2") (pintype "passive"))
      (node (ref "C347") (pin "2") (pinfunction "2_2") (pintype "passive"))
      (node (ref "DC/DC347") (pin "G") (pinfunction "G_G") (pintype "bidirectional"))
      (node (ref "IN-") (pin "1") (pinfunction "1_1") (pintype "passive"))
      (node (ref "M3B") (pin "S") (pinfunction "S_S") (pintype "passive"))
      (node (ref "M3BD") (pin "V-") (pinfunction "V-_V-") (pintype "bidirectional"))
      (node (ref "M4A") (pin "S") (pinfunction "S_S") (pintype "passive"))
      (node (ref "M4AD") (pin "V-") (pinfunction "V-_V-") (pintype "bidirectional"))
      (node (ref "M7B") (pin "S") (pinfunction "S_S") (pintype "passive"))
      (node (ref "M7BD") (pin "V-") (pinfunction "V-_V-") (pintype "bidirectional"))
      (node (ref "RIGHT") (pin "1") (pinfunction "1_1") (pintype "passive"))
      (node (ref "RS") (pin "2") (pinfunction "2_2") (pintype "passive"))
      (node (ref "U$3") (pin "R2") (pinfunction "R2_R2") (pintype "bidirectional"))
    )
    (net (code "43") (name "/SHUNTO{slash}P") (class "Default")
      (node (ref "ADC") (pin "CH1") (pinfunction "C1_CH1") (pintype "bidirectional"))
      (node (ref "O/P") (pin "1") (pinfunction "1_1") (pintype "passive"))
    )
    (net (code "44") (name "/TEMP") (class "Default")
      (node (ref "ADC") (pin "CH2") (pinfunction "C2_CH2") (pintype "bidirectional"))
      (node (ref "CELL") (pin "4") (pinfunction "4_4") (pintype "passive"))
      (node (ref "RTHERM") (pin "P$1") (pinfunction "1_P$1") (pintype "passive"))
    )
    (net (code "45") (name "/UCLK") (class "Default")
      (node (ref "HCPL902J") (pin "IN1") (pinfunction "IN1_IN1") (pintype "bidirectional"))
      (node (ref "UCON") (pin "2") (pinfunction "2_2") (pintype "passive"))
    )
    (net (code "46") (name "/UCS") (class "Default")
      (node (ref "HCPL902J") (pin "IN3") (pinfunction "IN3_IN3") (pintype "bidirectional"))
      (node (ref "UCON") (pin "4") (pinfunction "4_4") (pintype "passive"))
    )
    (net (code "47") (name "/UDIN") (class "Default")
      (node (ref "HCPL902J") (pin "IN2") (pinfunction "IN2_IN2") (pintype "bidirectional"))
      (node (ref "UCON") (pin "3") (pinfunction "3_3") (pintype "passive"))
    )
    (net (code "48") (name "/UDOUT") (class "Default")
      (node (ref "HCPL902J") (pin "OUT4") (pinfunction "O4_OUT4") (pintype "bidirectional"))
      (node (ref "UCON") (pin "5") (pinfunction "5_5") (pintype "passive"))
    )
    (net (code "49") (name "/V1+") (class "Default")
      (node (ref "C127") (pin "1") (pinfunction "1_1") (pintype "passive"))
      (node (ref "DC/DC127") (pin "V+") (pinfunction "V+_V+") (pintype "bidirectional"))
      (node (ref "M1BD") (pin "V+") (pinfunction "V+_V+") (pintype "bidirectional"))
      (node (ref "M2AD") (pin "V+") (pinfunction "V+_V+") (pintype "bidirectional"))
      (node (ref "M7AD") (pin "V+") (pinfunction "V+_V+") (pintype "bidirectional"))
    )
    (net (code "50") (name "/V1A") (class "Default")
      (node (ref "C1A") (pin "1") (pinfunction "1_1") (pintype "passive"))
      (node (ref "DC/DC1A") (pin "V+") (pinfunction "V+_V+") (pintype "bidirectional"))
      (node (ref "M1AD") (pin "V+") (pinfunction "V+_V+") (pintype "bidirectional"))
    )
    (net (code "51") (name "/V2+") (class "Default")
      (node (ref "C54B") (pin "1") (pinfunction "1_1") (pintype "passive"))
      (node (ref "DC/DC45") (pin "V+") (pinfunction "V+_V+") (pintype "bidirectional"))
      (node (ref "M4BD") (pin "V+") (pinfunction "V+_V+") (pintype "bidirectional"))
      (node (ref "M5D") (pin "V+") (pinfunction "V+_V+") (pintype "bidirectional"))
    )
    (net (code "52") (name "/V2B") (class "Default")
      (node (ref "C2B") (pin "1") (pinfunction "1_1") (pintype "passive"))
      (node (ref "DC/DC2B") (pin "V+") (pinfunction "V+_V+") (pintype "bidirectional"))
      (node (ref "M2BD") (pin "V+") (pinfunction "V+_V+") (pintype "bidirectional"))
    )
    (net (code "53") (name "/V3+") (class "Default")
      (node (ref "C347") (pin "1") (pinfunction "1_1") (pintype "passive"))
      (node (ref "DC/DC347") (pin "V+") (pinfunction "V+_V+") (pintype "bidirectional"))
      (node (ref "M3BD") (pin "V+") (pinfunction "V+_V+") (pintype "bidirectional"))
      (node (ref "M4AD") (pin "V+") (pinfunction "V+_V+") (pintype "bidirectional"))
      (node (ref "M7BD") (pin "V+") (pinfunction "V+_V+") (pintype "bidirectional"))
    )
    (net (code "54") (name "/V3A") (class "Default")
      (node (ref "C3A") (pin "1") (pinfunction "1_1") (pintype "passive"))
      (node (ref "DC/DC3A") (pin "V+") (pinfunction "V+_V+") (pintype "bidirectional"))
      (node (ref "M3AD") (pin "V+") (pinfunction "V+_V+") (pintype "bidirectional"))
    )
    (net (code "55") (name "/V6") (class "Default")
      (node (ref "C6") (pin "1") (pinfunction "1_1") (pintype "passive"))
      (node (ref "DC/DC6") (pin "V+") (pinfunction "V+_V+") (pintype "bidirectional"))
      (node (ref "M6D") (pin "V+") (pinfunction "V+_V+") (pintype "bidirectional"))
    )
    (net (code "56") (name "/VISO") (class "Default")
      (node (ref "CISO") (pin "2") (pinfunction "2_2") (pintype "passive"))
      (node (ref "HCPL902J") (pin "V1") (pinfunction "V1_V1") (pintype "bidirectional"))
      (node (ref "UCON") (pin "1") (pinfunction "1_1") (pintype "passive"))
    )
    (net (code "57") (name "/VREG+") (class "Default")
      (node (ref "2937ET") (pin "IN") (pinfunction "IN_IN") (pintype "input"))
      (node (ref "DC/DC-ADC") (pin "V+") (pinfunction "V+_V+") (pintype "bidirectional"))
      (node (ref "INA117") (pin "7") (pinfunction "V+_7") (pintype "power_in"))
    )
    (net (code "58") (name "/VREG-") (class "Default")
      (node (ref "DC/DC-ADC") (pin "V-") (pinfunction "V-_V-") (pintype "bidirectional"))
      (node (ref "INA117") (pin "4") (pinfunction "V-_4") (pintype "power_in"))
    )
    (net (code "59") (name "Net-(1A-1)") (class "Default")
      (node (ref "1A") (pin "P$1") (pinfunction "1_P$1") (pintype "passive"))
      (node (ref "UCON") (pin "7") (pinfunction "7_7") (pintype "passive"))
    )
    (net (code "60") (name "Net-(1B-1)") (class "Default")
      (node (ref "1B") (pin "P$1") (pinfunction "1_P$1") (pintype "passive"))
      (node (ref "UCON") (pin "8") (pinfunction "8_8") (pintype "passive"))
    )
    (net (code "61") (name "Net-(2A-1)") (class "Default")
      (node (ref "2A") (pin "P$1") (pinfunction "1_P$1") (pintype "passive"))
      (node (ref "UCON") (pin "9") (pinfunction "9_9") (pintype "passive"))
    )
    (net (code "62") (name "Net-(2B-1)") (class "Default")
      (node (ref "2B") (pin "P$1") (pinfunction "1_P$1") (pintype "passive"))
      (node (ref "UCON") (pin "10") (pinfunction "10_10") (pintype "passive"))
    )
    (net (code "63") (name "Net-(3A-1)") (class "Default")
      (node (ref "3A") (pin "P$1") (pinfunction "1_P$1") (pintype "passive"))
      (node (ref "UCON") (pin "11") (pinfunction "11_11") (pintype "passive"))
    )
    (net (code "64") (name "Net-(3B-1)") (class "Default")
      (node (ref "3B") (pin "P$1") (pinfunction "1_P$1") (pintype "passive"))
      (node (ref "UCON") (pin "12") (pinfunction "12_12") (pintype "passive"))
    )
    (net (code "65") (name "Net-(4A-1)") (class "Default")
      (node (ref "4A") (pin "P$1") (pinfunction "1_P$1") (pintype "passive"))
      (node (ref "UCON") (pin "13") (pinfunction "13_13") (pintype "passive"))
    )
    (net (code "66") (name "Net-(4B-1)") (class "Default")
      (node (ref "4B") (pin "P$1") (pinfunction "1_P$1") (pintype "passive"))
      (node (ref "UCON") (pin "14") (pinfunction "14_14") (pintype "passive"))
    )
    (net (code "67") (name "Net-(5-1)") (class "Default")
      (node (ref "5") (pin "P$1") (pinfunction "1_P$1") (pintype "passive"))
      (node (ref "UCON") (pin "15") (pinfunction "15_15") (pintype "passive"))
    )
    (net (code "68") (name "Net-(6-1)") (class "Default")
      (node (ref "6") (pin "P$1") (pinfunction "1_P$1") (pintype "passive"))
      (node (ref "UCON") (pin "16") (pinfunction "16_16") (pintype "passive"))
    )
    (net (code "69") (name "Net-(7A-1)") (class "Default")
      (node (ref "7A") (pin "P$1") (pinfunction "1_P$1") (pintype "passive"))
      (node (ref "UCON") (pin "17") (pinfunction "17_17") (pintype "passive"))
    )
    (net (code "70") (name "Net-(7B-1)") (class "Default")
      (node (ref "7B") (pin "P$1") (pinfunction "1_P$1") (pintype "passive"))
      (node (ref "UCON") (pin "18") (pinfunction "18_18") (pintype "passive"))
    )
    (net (code "71") (name "Net-(AD8210-PadGND)") (class "Default")
      (node (ref "AD8210") (pin "GND") (pinfunction "GND_GND") (pintype "bidirectional"))
      (node (ref "GND") (pin "2") (pinfunction "2_2") (pintype "passive"))
    )
    (net (code "72") (name "Net-(AD8210-PadIN+)") (class "Default")
      (node (ref "AD8210") (pin "IN+") (pinfunction "IN+_IN+") (pintype "bidirectional"))
      (node (ref "IN+") (pin "2") (pinfunction "2_2") (pintype "passive"))
    )
    (net (code "73") (name "Net-(AD8210-PadIN-)") (class "Default")
      (node (ref "AD8210") (pin "IN-") (pinfunction "IN-_IN-") (pintype "bidirectional"))
      (node (ref "IN-") (pin "2") (pinfunction "2_2") (pintype "passive"))
    )
    (net (code "74") (name "Net-(AD8210-PadO{slash}P)") (class "Default")
      (node (ref "AD8210") (pin "O/P") (pinfunction "O/P_O/P") (pintype "bidirectional"))
      (node (ref "O/P") (pin "2") (pinfunction "2_2") (pintype "passive"))
    )
    (net (code "75") (name "Net-(AD8210-PadV+)") (class "Default")
      (node (ref "AD8210") (pin "V+") (pinfunction "V+_V+") (pintype "bidirectional"))
      (node (ref "VDD") (pin "2") (pinfunction "2_2") (pintype "passive"))
    )
    (net (code "76") (name "Net-(AD8210-PadVR1)") (class "Default")
      (node (ref "AD8210") (pin "VR1") (pinfunction "VR1_VR1") (pintype "bidirectional"))
      (node (ref "VR1") (pin "2") (pinfunction "2_2") (pintype "passive"))
    )
    (net (code "77") (name "Net-(AD8210-PadVR2)") (class "Default")
      (node (ref "AD8210") (pin "VR2") (pinfunction "VR2_VR2") (pintype "bidirectional"))
      (node (ref "VR2") (pin "2") (pinfunction "2_2") (pintype "passive"))
    )
    (net (code "78") (name "Net-(LED1-PadA)") (class "Default")
      (node (ref "LED1") (pin "A") (pinfunction "A_A") (pintype "passive"))
      (node (ref "R1") (pin "2") (pinfunction "2_2") (pintype "passive"))
    )
    (net (code "79") (name "Net-(LED2-PadA)") (class "Default")
      (node (ref "LED2") (pin "A") (pinfunction "A_A") (pintype "passive"))
      (node (ref "R2") (pin "2") (pinfunction "2_2") (pintype "passive"))
    )
    (net (code "80") (name "Net-(LED3-PadA)") (class "Default")
      (node (ref "LED3") (pin "A") (pinfunction "A_A") (pintype "passive"))
      (node (ref "R3") (pin "2") (pinfunction "2_2") (pintype "passive"))
    )
    (net (code "81") (name "Net-(LED4-PadA)") (class "Default")
      (node (ref "LED4") (pin "A") (pinfunction "A_A") (pintype "passive"))
      (node (ref "R4") (pin "2") (pinfunction "2_2") (pintype "passive"))
    )
    (net (code "82") (name "Net-(M1A-PadD)") (class "Default")
      (node (ref "M1A") (pin "D") (pinfunction "D_D") (pintype "passive"))
      (node (ref "M1B") (pin "D") (pinfunction "D_D") (pintype "passive"))
    )
    (net (code "83") (name "Net-(M2A-PadD)") (class "Default")
      (node (ref "M2A") (pin "D") (pinfunction "D_D") (pintype "passive"))
      (node (ref "M2B") (pin "D") (pinfunction "D_D") (pintype "passive"))
    )
    (net (code "84") (name "Net-(M3A-PadD)") (class "Default")
      (node (ref "M3A") (pin "D") (pinfunction "D_D") (pintype "passive"))
      (node (ref "M3B") (pin "D") (pinfunction "D_D") (pintype "passive"))
    )
    (net (code "85") (name "Net-(M4A-PadD)") (class "Default")
      (node (ref "M4A") (pin "D") (pinfunction "D_D") (pintype "passive"))
      (node (ref "M4B") (pin "D") (pinfunction "D_D") (pintype "passive"))
    )
    (net (code "86") (name "Net-(M7A-PadD)") (class "Default")
      (node (ref "M7A") (pin "D") (pinfunction "D_D") (pintype "passive"))
      (node (ref "M7B") (pin "D") (pinfunction "D_D") (pintype "passive"))
    )
    (net (code "87") (name "Net-(R1-Pad1)") (class "Default")
      (node (ref "R1") (pin "1") (pinfunction "1_1") (pintype "passive"))
      (node (ref "UCON") (pin "20") (pinfunction "20_20") (pintype "passive"))
    )
    (net (code "88") (name "Net-(R2-Pad1)") (class "Default")
      (node (ref "R2") (pin "1") (pinfunction "1_1") (pintype "passive"))
      (node (ref "UCON") (pin "21") (pinfunction "21_21") (pintype "passive"))
    )
    (net (code "89") (name "Net-(R3-Pad1)") (class "Default")
      (node (ref "R3") (pin "1") (pinfunction "1_1") (pintype "passive"))
      (node (ref "UCON") (pin "22") (pinfunction "22_22") (pintype "passive"))
    )
    (net (code "90") (name "Net-(R4-Pad1)") (class "Default")
      (node (ref "R4") (pin "1") (pinfunction "1_1") (pintype "passive"))
      (node (ref "UCON") (pin "23") (pinfunction "23_23") (pintype "passive"))
    )
    (net (code "91") (name "unconnected-(AD8210-PadNC)") (class "Default")
      (node (ref "AD8210") (pin "NC") (pinfunction "NC_NC") (pintype "bidirectional"))
    )
    (net (code "92") (name "unconnected-(ADC-C3-PadCH3)") (class "Default")
      (node (ref "ADC") (pin "CH3") (pinfunction "C3_CH3") (pintype "bidirectional"))
    )
    (net (code "93") (name "unconnected-(ADC-Pad6)") (class "Default")
      (node (ref "ADC") (pin "6") (pinfunction "6_6") (pintype "bidirectional"))
    )
    (net (code "94") (name "unconnected-(ADC-PadNC)") (class "Default")
      (node (ref "ADC") (pin "NC") (pinfunction "NC_NC") (pintype "bidirectional"))
    )
    (net (code "95") (name "unconnected-(DC/DC1A-PadV-)") (class "Default")
      (node (ref "DC/DC1A") (pin "V-") (pinfunction "V-_V-") (pintype "bidirectional"))
    )
    (net (code "96") (name "unconnected-(DC/DC2B-PadV-)") (class "Default")
      (node (ref "DC/DC2B") (pin "V-") (pinfunction "V-_V-") (pintype "bidirectional"))
    )
    (net (code "97") (name "unconnected-(DC/DC3A-PadV-)") (class "Default")
      (node (ref "DC/DC3A") (pin "V-") (pinfunction "V-_V-") (pintype "bidirectional"))
    )
    (net (code "98") (name "unconnected-(DC/DC6-PadV-)") (class "Default")
      (node (ref "DC/DC6") (pin "V-") (pinfunction "V-_V-") (pintype "bidirectional"))
    )
    (net (code "99") (name "unconnected-(DC/DC45-PadV-)") (class "Default")
      (node (ref "DC/DC45") (pin "V-") (pinfunction "V-_V-") (pintype "bidirectional"))
    )
    (net (code "100") (name "unconnected-(DC/DC127-PadV-)") (class "Default")
      (node (ref "DC/DC127") (pin "V-") (pinfunction "V-_V-") (pintype "bidirectional"))
    )
    (net (code "101") (name "unconnected-(DC/DC347-PadV-)") (class "Default")
      (node (ref "DC/DC347") (pin "V-") (pinfunction "V-_V-") (pintype "bidirectional"))
    )
    (net (code "102") (name "unconnected-(HCPL902J-PadN1)") (class "Default")
      (node (ref "HCPL902J") (pin "N1") (pinfunction "N1_N1") (pintype "bidirectional"))
    )
    (net (code "103") (name "unconnected-(HCPL902J-PadN2)") (class "Default")
      (node (ref "HCPL902J") (pin "N2") (pinfunction "N2_N2") (pintype "bidirectional"))
    )
    (net (code "104") (name "unconnected-(M1AD-Pad1)") (class "Default")
      (node (ref "M1AD") (pin "1") (pinfunction "1_1") (pintype "bidirectional"))
    )
    (net (code "105") (name "unconnected-(M1AD-Pad4)") (class "Default")
      (node (ref "M1AD") (pin "4") (pinfunction "4_4") (pintype "bidirectional"))
    )
    (net (code "106") (name "unconnected-(M1AD-Pad6)") (class "Default")
      (node (ref "M1AD") (pin "6") (pinfunction "6_6") (pintype "bidirectional"))
    )
    (net (code "107") (name "unconnected-(M1BD-Pad1)") (class "Default")
      (node (ref "M1BD") (pin "1") (pinfunction "1_1") (pintype "bidirectional"))
    )
    (net (code "108") (name "unconnected-(M1BD-Pad4)") (class "Default")
      (node (ref "M1BD") (pin "4") (pinfunction "4_4") (pintype "bidirectional"))
    )
    (net (code "109") (name "unconnected-(M1BD-Pad6)") (class "Default")
      (node (ref "M1BD") (pin "6") (pinfunction "6_6") (pintype "bidirectional"))
    )
    (net (code "110") (name "unconnected-(M2AD-Pad1)") (class "Default")
      (node (ref "M2AD") (pin "1") (pinfunction "1_1") (pintype "bidirectional"))
    )
    (net (code "111") (name "unconnected-(M2AD-Pad4)") (class "Default")
      (node (ref "M2AD") (pin "4") (pinfunction "4_4") (pintype "bidirectional"))
    )
    (net (code "112") (name "unconnected-(M2AD-Pad6)") (class "Default")
      (node (ref "M2AD") (pin "6") (pinfunction "6_6") (pintype "bidirectional"))
    )
    (net (code "113") (name "unconnected-(M2BD-Pad1)") (class "Default")
      (node (ref "M2BD") (pin "1") (pinfunction "1_1") (pintype "bidirectional"))
    )
    (net (code "114") (name "unconnected-(M2BD-Pad4)") (class "Default")
      (node (ref "M2BD") (pin "4") (pinfunction "4_4") (pintype "bidirectional"))
    )
    (net (code "115") (name "unconnected-(M2BD-Pad6)") (class "Default")
      (node (ref "M2BD") (pin "6") (pinfunction "6_6") (pintype "bidirectional"))
    )
    (net (code "116") (name "unconnected-(M3AD-Pad1)") (class "Default")
      (node (ref "M3AD") (pin "1") (pinfunction "1_1") (pintype "bidirectional"))
    )
    (net (code "117") (name "unconnected-(M3AD-Pad4)") (class "Default")
      (node (ref "M3AD") (pin "4") (pinfunction "4_4") (pintype "bidirectional"))
    )
    (net (code "118") (name "unconnected-(M3AD-Pad6)") (class "Default")
      (node (ref "M3AD") (pin "6") (pinfunction "6_6") (pintype "bidirectional"))
    )
    (net (code "119") (name "unconnected-(M3BD-Pad1)") (class "Default")
      (node (ref "M3BD") (pin "1") (pinfunction "1_1") (pintype "bidirectional"))
    )
    (net (code "120") (name "unconnected-(M3BD-Pad4)") (class "Default")
      (node (ref "M3BD") (pin "4") (pinfunction "4_4") (pintype "bidirectional"))
    )
    (net (code "121") (name "unconnected-(M3BD-Pad6)") (class "Default")
      (node (ref "M3BD") (pin "6") (pinfunction "6_6") (pintype "bidirectional"))
    )
    (net (code "122") (name "unconnected-(M4AD-Pad1)") (class "Default")
      (node (ref "M4AD") (pin "1") (pinfunction "1_1") (pintype "bidirectional"))
    )
    (net (code "123") (name "unconnected-(M4AD-Pad4)") (class "Default")
      (node (ref "M4AD") (pin "4") (pinfunction "4_4") (pintype "bidirectional"))
    )
    (net (code "124") (name "unconnected-(M4AD-Pad6)") (class "Default")
      (node (ref "M4AD") (pin "6") (pinfunction "6_6") (pintype "bidirectional"))
    )
    (net (code "125") (name "unconnected-(M4BD-Pad1)") (class "Default")
      (node (ref "M4BD") (pin "1") (pinfunction "1_1") (pintype "bidirectional"))
    )
    (net (code "126") (name "unconnected-(M4BD-Pad4)") (class "Default")
      (node (ref "M4BD") (pin "4") (pinfunction "4_4") (pintype "bidirectional"))
    )
    (net (code "127") (name "unconnected-(M4BD-Pad6)") (class "Default")
      (node (ref "M4BD") (pin "6") (pinfunction "6_6") (pintype "bidirectional"))
    )
    (net (code "128") (name "unconnected-(M5D-Pad1)") (class "Default")
      (node (ref "M5D") (pin "1") (pinfunction "1_1") (pintype "bidirectional"))
    )
    (net (code "129") (name "unconnected-(M5D-Pad4)") (class "Default")
      (node (ref "M5D") (pin "4") (pinfunction "4_4") (pintype "bidirectional"))
    )
    (net (code "130") (name "unconnected-(M5D-Pad6)") (class "Default")
      (node (ref "M5D") (pin "6") (pinfunction "6_6") (pintype "bidirectional"))
    )
    (net (code "131") (name "unconnected-(M6D-Pad1)") (class "Default")
      (node (ref "M6D") (pin "1") (pinfunction "1_1") (pintype "bidirectional"))
    )
    (net (code "132") (name "unconnected-(M6D-Pad4)") (class "Default")
      (node (ref "M6D") (pin "4") (pinfunction "4_4") (pintype "bidirectional"))
    )
    (net (code "133") (name "unconnected-(M6D-Pad6)") (class "Default")
      (node (ref "M6D") (pin "6") (pinfunction "6_6") (pintype "bidirectional"))
    )
    (net (code "134") (name "unconnected-(M7AD-Pad1)") (class "Default")
      (node (ref "M7AD") (pin "1") (pinfunction "1_1") (pintype "bidirectional"))
    )
    (net (code "135") (name "unconnected-(M7AD-Pad4)") (class "Default")
      (node (ref "M7AD") (pin "4") (pinfunction "4_4") (pintype "bidirectional"))
    )
    (net (code "136") (name "unconnected-(M7AD-Pad6)") (class "Default")
      (node (ref "M7AD") (pin "6") (pinfunction "6_6") (pintype "bidirectional"))
    )
    (net (code "137") (name "unconnected-(M7BD-Pad1)") (class "Default")
      (node (ref "M7BD") (pin "1") (pinfunction "1_1") (pintype "bidirectional"))
    )
    (net (code "138") (name "unconnected-(M7BD-Pad4)") (class "Default")
      (node (ref "M7BD") (pin "4") (pinfunction "4_4") (pintype "bidirectional"))
    )
    (net (code "139") (name "unconnected-(M7BD-Pad6)") (class "Default")
      (node (ref "M7BD") (pin "6") (pinfunction "6_6") (pintype "bidirectional"))
    )
    (net (code "140") (name "unconnected-(U$21-PadRING_SW)") (class "Default")
      (node (ref "U$21") (pin "RING_SW") (pinfunction "RING_SW_RING_SW") (pintype "bidirectional"))
    )
    (net (code "141") (name "unconnected-(UCON-Pad24)") (class "Default")
      (node (ref "UCON") (pin "24") (pinfunction "24_24") (pintype "passive"))
    )
    (net (code "142") (name "unconnected-(UCON-Pad25)") (class "Default")
      (node (ref "UCON") (pin "25") (pinfunction "25_25") (pintype "passive"))
    )
  )
)
